# MCU.net
KiCad netlist of a schematic drawn in Altium Designer
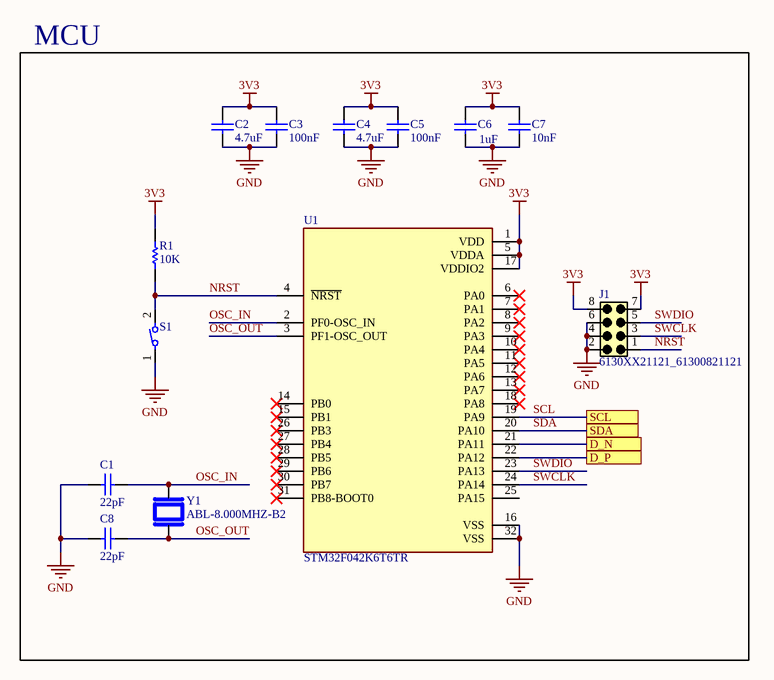
[diagram p0: MCU.SchDoc]

(export (version "E")
  (design (tool "Eeschema 10.0.6"))
  (components
    (comp (ref "C1")
      (value "22pF")
      (footprint "CAP_0402L")
      (description "CAP CER 22pF 16V X7R 10% 0402")
      (fields (field (name "TOLERANCE") "10%"))
      (libsource (lib "PCB_training_Project") (part "CAP CER 22pF"))
    )
    (comp (ref "C2")
      (value "4.7uF")
      (footprint "CAP_0402L")
      (description "CAP CER 4.7uF 16V X7R 10% 0402")
      (fields (field (name "TOLERANCE") "10%"))
      (libsource (lib "PCB_training_Project") (part "CAP CER 4.7uF"))
    )
    (comp (ref "C3")
      (value "100nF")
      (footprint "CAP_0402L")
      (description "CAP CER 100nF 16V X7R 10% 0402")
      (fields (field (name "TOLERANCE") "10%"))
      (libsource (lib "PCB_training_Project") (part "CAP CER 100nF"))
    )
    (comp (ref "C4")
      (value "4.7uF")
      (footprint "CAP_0402L")
      (description "CAP CER 4.7uF 16V X7R 10% 0402")
      (fields (field (name "TOLERANCE") "10%"))
      (libsource (lib "PCB_training_Project") (part "CAP CER 4.7uF"))
    )
    (comp (ref "C5")
      (value "100nF")
      (footprint "CAP_0402L")
      (description "CAP CER 100nF 16V X7R 10% 0402")
      (fields (field (name "TOLERANCE") "10%"))
      (libsource (lib "PCB_training_Project") (part "CAP CER 100nF"))
    )
    (comp (ref "C6")
      (value "1uF")
      (footprint "CAP_0402L")
      (description "CAP CER 100nF 16V X7R 10% 0402")
      (fields (field (name "TOLERANCE") "10%"))
      (libsource (lib "PCB_training_Project") (part "CAP CER 100nF_1"))
    )
    (comp (ref "C7")
      (value "10nF")
      (footprint "CAP_0402L")
      (description "CAP CER 100nF 16V X7R 10% 0402")
      (fields (field (name "TOLERANCE") "10%"))
      (libsource (lib "PCB_training_Project") (part "CAP CER 100nF"))
    )
    (comp (ref "C8")
      (value "22pF")
      (footprint "CAP_0402L")
      (description "CAP CER 22pF 16V X7R 10% 0402")
      (fields (field (name "TOLERANCE") "10%"))
      (libsource (lib "PCB_training_Project") (part "CAP CER 22pF"))
    )
    (comp (ref "J1")
      (value "6130XX21121_61300821121")
      (footprint "61300821121")
      (description "Connector Header Through Hole 8 position 0.100 (2.54mm)")
      (fields (field (name "MF") "Wurth Electronics") (field (name "MP") "61300821121"))
      (libsource (lib "PCB_training_Project") (part "6130XX21121_61300821121"))
    )
    (comp (ref "R1")
      (value "10K")
      (footprint "RES_0402N")
      (description "RES SMD 10K OHM 1% 1/16W 0402")
      (fields (field (name "TOLERANCE") "1%"))
      (libsource (lib "PCB_training_Project") (part "RES SMD 10K"))
    )
    (comp (ref "S1")
      (value "434123025816")
      (footprint "434123025816")
      (description "Tactile Switch SPST-NO Top Actuated Surface Mount")
      (fields (field (name "MF") "WÃ¼rth Elektronik"))
      (libsource (lib "PCB_training_Project") (part "434123025816"))
    )
    (comp (ref "U1")
      (value "STM32F042K6T6TR")
      (footprint "QFP80P900X900X160-32N")
      (fields (field (name "MF") "STMicroelectronics"))
      (libsource (lib "PCB_training_Project") (part "STM32F042K6T6TR"))
    )
    (comp (ref "Y1")
      (value "ABL-8.000MHZ-B2")
      (footprint "XTAL_HC49P488W46L1150T500H350")
      (description "HC/49US (AT49) MICROPROCESSOR CRYSTAL")
      (fields (field (name "MF") "Abracon"))
      (libsource (lib "PCB_training_Project") (part "ABL-8.000MHZ-B2"))
    )
  )
  (nets
    (net (code "1") (name "/D_N") (class "Default")
      (node (ref "U1") (pin "21") (pinfunction "PA11_21") (pintype "passive"))
    )
    (net (code "2") (name "/D_P") (class "Default")
      (node (ref "U1") (pin "22") (pinfunction "PA12_22") (pintype "passive"))
    )
    (net (code "3") (name "/NRST") (class "Default")
      (node (ref "J1") (pin "1") (pinfunction "1_1") (pintype "passive"))
      (node (ref "R1") (pin "1") (pinfunction "1_1") (pintype "passive"))
      (node (ref "S1") (pin "2") (pinfunction "2_2") (pintype "passive"))
      (node (ref "U1") (pin "4") (pinfunction "~{NRST}_4") (pintype "passive"))
    )
    (net (code "4") (name "/OSC_IN") (class "Default")
      (node (ref "C1") (pin "2") (pinfunction "2_2") (pintype "passive"))
      (node (ref "U1") (pin "2") (pinfunction "PF0-OSC_IN_2") (pintype "passive"))
      (node (ref "Y1") (pin "2") (pinfunction "2_2") (pintype "passive"))
    )
    (net (code "5") (name "/OSC_OUT") (class "Default")
      (node (ref "C8") (pin "2") (pinfunction "2_2") (pintype "passive"))
      (node (ref "U1") (pin "3") (pinfunction "PF1-OSC_OUT_3") (pintype "passive"))
      (node (ref "Y1") (pin "1") (pinfunction "1_1") (pintype "passive"))
    )
    (net (code "6") (name "/SCL") (class "Default")
      (node (ref "U1") (pin "19") (pinfunction "PA9_19") (pintype "passive"))
    )
    (net (code "7") (name "/SDA") (class "Default")
      (node (ref "U1") (pin "20") (pinfunction "PA10_20") (pintype "passive"))
    )
    (net (code "8") (name "/SWCLK") (class "Default")
      (node (ref "J1") (pin "3") (pinfunction "3_3") (pintype "passive"))
      (node (ref "U1") (pin "24") (pinfunction "PA14_24") (pintype "passive"))
    )
    (net (code "9") (name "/SWDIO") (class "Default")
      (node (ref "J1") (pin "5") (pinfunction "5_5") (pintype "passive"))
      (node (ref "U1") (pin "23") (pinfunction "PA13_23") (pintype "passive"))
    )
    (net (code "10") (name "3V3") (class "Default")
      (node (ref "C2") (pin "2") (pinfunction "2_2") (pintype "passive"))
      (node (ref "C3") (pin "2") (pinfunction "2_2") (pintype "passive"))
      (node (ref "C4") (pin "2") (pinfunction "2_2") (pintype "passive"))
      (node (ref "C5") (pin "2") (pinfunction "2_2") (pintype "passive"))
      (node (ref "C6") (pin "2") (pinfunction "2_2") (pintype "passive"))
      (node (ref "C7") (pin "2") (pinfunction "2_2") (pintype "passive"))
      (node (ref "J1") (pin "7") (pinfunction "7_7") (pintype "passive"))
      (node (ref "J1") (pin "8") (pinfunction "8_8") (pintype "passive"))
      (node (ref "R1") (pin "2") (pinfunction "2_2") (pintype "passive"))
      (node (ref "U1") (pin "1") (pinfunction "VDD_1") (pintype "passive"))
      (node (ref "U1") (pin "17") (pinfunction "VDDIO2_17") (pintype "passive"))
      (node (ref "U1") (pin "5") (pinfunction "VDDA_5") (pintype "passive"))
    )
    (net (code "11") (name "GND") (class "Default")
      (node (ref "C1") (pin "1") (pinfunction "1_1") (pintype "passive"))
      (node (ref "C2") (pin "1") (pinfunction "1_1") (pintype "passive"))
      (node (ref "C3") (pin "1") (pinfunction "1_1") (pintype "passive"))
      (node (ref "C4") (pin "1") (pinfunction "1_1") (pintype "passive"))
      (node (ref "C5") (pin "1") (pinfunction "1_1") (pintype "passive"))
      (node (ref "C6") (pin "1") (pinfunction "1_1") (pintype "passive"))
      (node (ref "C7") (pin "1") (pinfunction "1_1") (pintype "passive"))
      (node (ref "C8") (pin "1") (pinfunction "1_1") (pintype "passive"))
      (node (ref "J1") (pin "2") (pinfunction "2_2") (pintype "passive"))
      (node (ref "J1") (pin "4") (pinfunction "4_4") (pintype "passive"))
      (node (ref "J1") (pin "6") (pinfunction "6_6") (pintype "passive"))
      (node (ref "S1") (pin "1") (pinfunction "1_1") (pintype "passive"))
      (node (ref "U1") (pin "16") (pinfunction "VSS_16") (pintype "passive"))
      (node (ref "U1") (pin "32") (pinfunction "VSS_32") (pintype "passive"))
    )
    (net (code "12") (name "unconnected-(U1-PA0-Pad6)") (class "Default")
      (node (ref "U1") (pin "6") (pinfunction "PA0_6") (pintype "passive+no_connect"))
    )
    (net (code "13") (name "unconnected-(U1-PA1-Pad7)") (class "Default")
      (node (ref "U1") (pin "7") (pinfunction "PA1_7") (pintype "passive+no_connect"))
    )
    (net (code "14") (name "unconnected-(U1-PA2-Pad8)") (class "Default")
      (node (ref "U1") (pin "8") (pinfunction "PA2_8") (pintype "passive+no_connect"))
    )
    (net (code "15") (name "unconnected-(U1-PA3-Pad9)") (class "Default")
      (node (ref "U1") (pin "9") (pinfunction "PA3_9") (pintype "passive+no_connect"))
    )
    (net (code "16") (name "unconnected-(U1-PA4-Pad10)") (class "Default")
      (node (ref "U1") (pin "10") (pinfunction "PA4_10") (pintype "passive+no_connect"))
    )
    (net (code "17") (name "unconnected-(U1-PA5-Pad11)") (class "Default")
      (node (ref "U1") (pin "11") (pinfunction "PA5_11") (pintype "passive+no_connect"))
    )
    (net (code "18") (name "unconnected-(U1-PA6-Pad12)") (class "Default")
      (node (ref "U1") (pin "12") (pinfunction "PA6_12") (pintype "passive+no_connect"))
    )
    (net (code "19") (name "unconnected-(U1-PA7-Pad13)") (class "Default")
      (node (ref "U1") (pin "13") (pinfunction "PA7_13") (pintype "passive+no_connect"))
    )
    (net (code "20") (name "unconnected-(U1-PA8-Pad18)") (class "Default")
      (node (ref "U1") (pin "18") (pinfunction "PA8_18") (pintype "passive+no_connect"))
    )
    (net (code "21") (name "unconnected-(U1-PA15-Pad25)") (class "Default")
      (node (ref "U1") (pin "25") (pinfunction "PA15_25") (pintype "passive"))
    )
    (net (code "22") (name "unconnected-(U1-PB0-Pad14)") (class "Default")
      (node (ref "U1") (pin "14") (pinfunction "PB0_14") (pintype "passive+no_connect"))
    )
    (net (code "23") (name "unconnected-(U1-PB1-Pad15)") (class "Default")
      (node (ref "U1") (pin "15") (pinfunction "PB1_15") (pintype "passive+no_connect"))
    )
    (net (code "24") (name "unconnected-(U1-PB3-Pad26)") (class "Default")
      (node (ref "U1") (pin "26") (pinfunction "PB3_26") (pintype "passive+no_connect"))
    )
    (net (code "25") (name "unconnected-(U1-PB4-Pad27)") (class "Default")
      (node (ref "U1") (pin "27") (pinfunction "PB4_27") (pintype "passive+no_connect"))
    )
    (net (code "26") (name "unconnected-(U1-PB5-Pad28)") (class "Default")
      (node (ref "U1") (pin "28") (pinfunction "PB5_28") (pintype "passive+no_connect"))
    )
    (net (code "27") (name "unconnected-(U1-PB6-Pad29)") (class "Default")
      (node (ref "U1") (pin "29") (pinfunction "PB6_29") (pintype "passive+no_connect"))
    )
    (net (code "28") (name "unconnected-(U1-PB7-Pad30)") (class "Default")
      (node (ref "U1") (pin "30") (pinfunction "PB7_30") (pintype "passive+no_connect"))
    )
    (net (code "29") (name "unconnected-(U1-PB8-BOOT0-Pad31)") (class "Default")
      (node (ref "U1") (pin "31") (pinfunction "PB8-BOOT0_31") (pintype "passive+no_connect"))
    )
  )
)
